# NanoShield.net
KiCad netlist of a schematic drawn in EAGLE
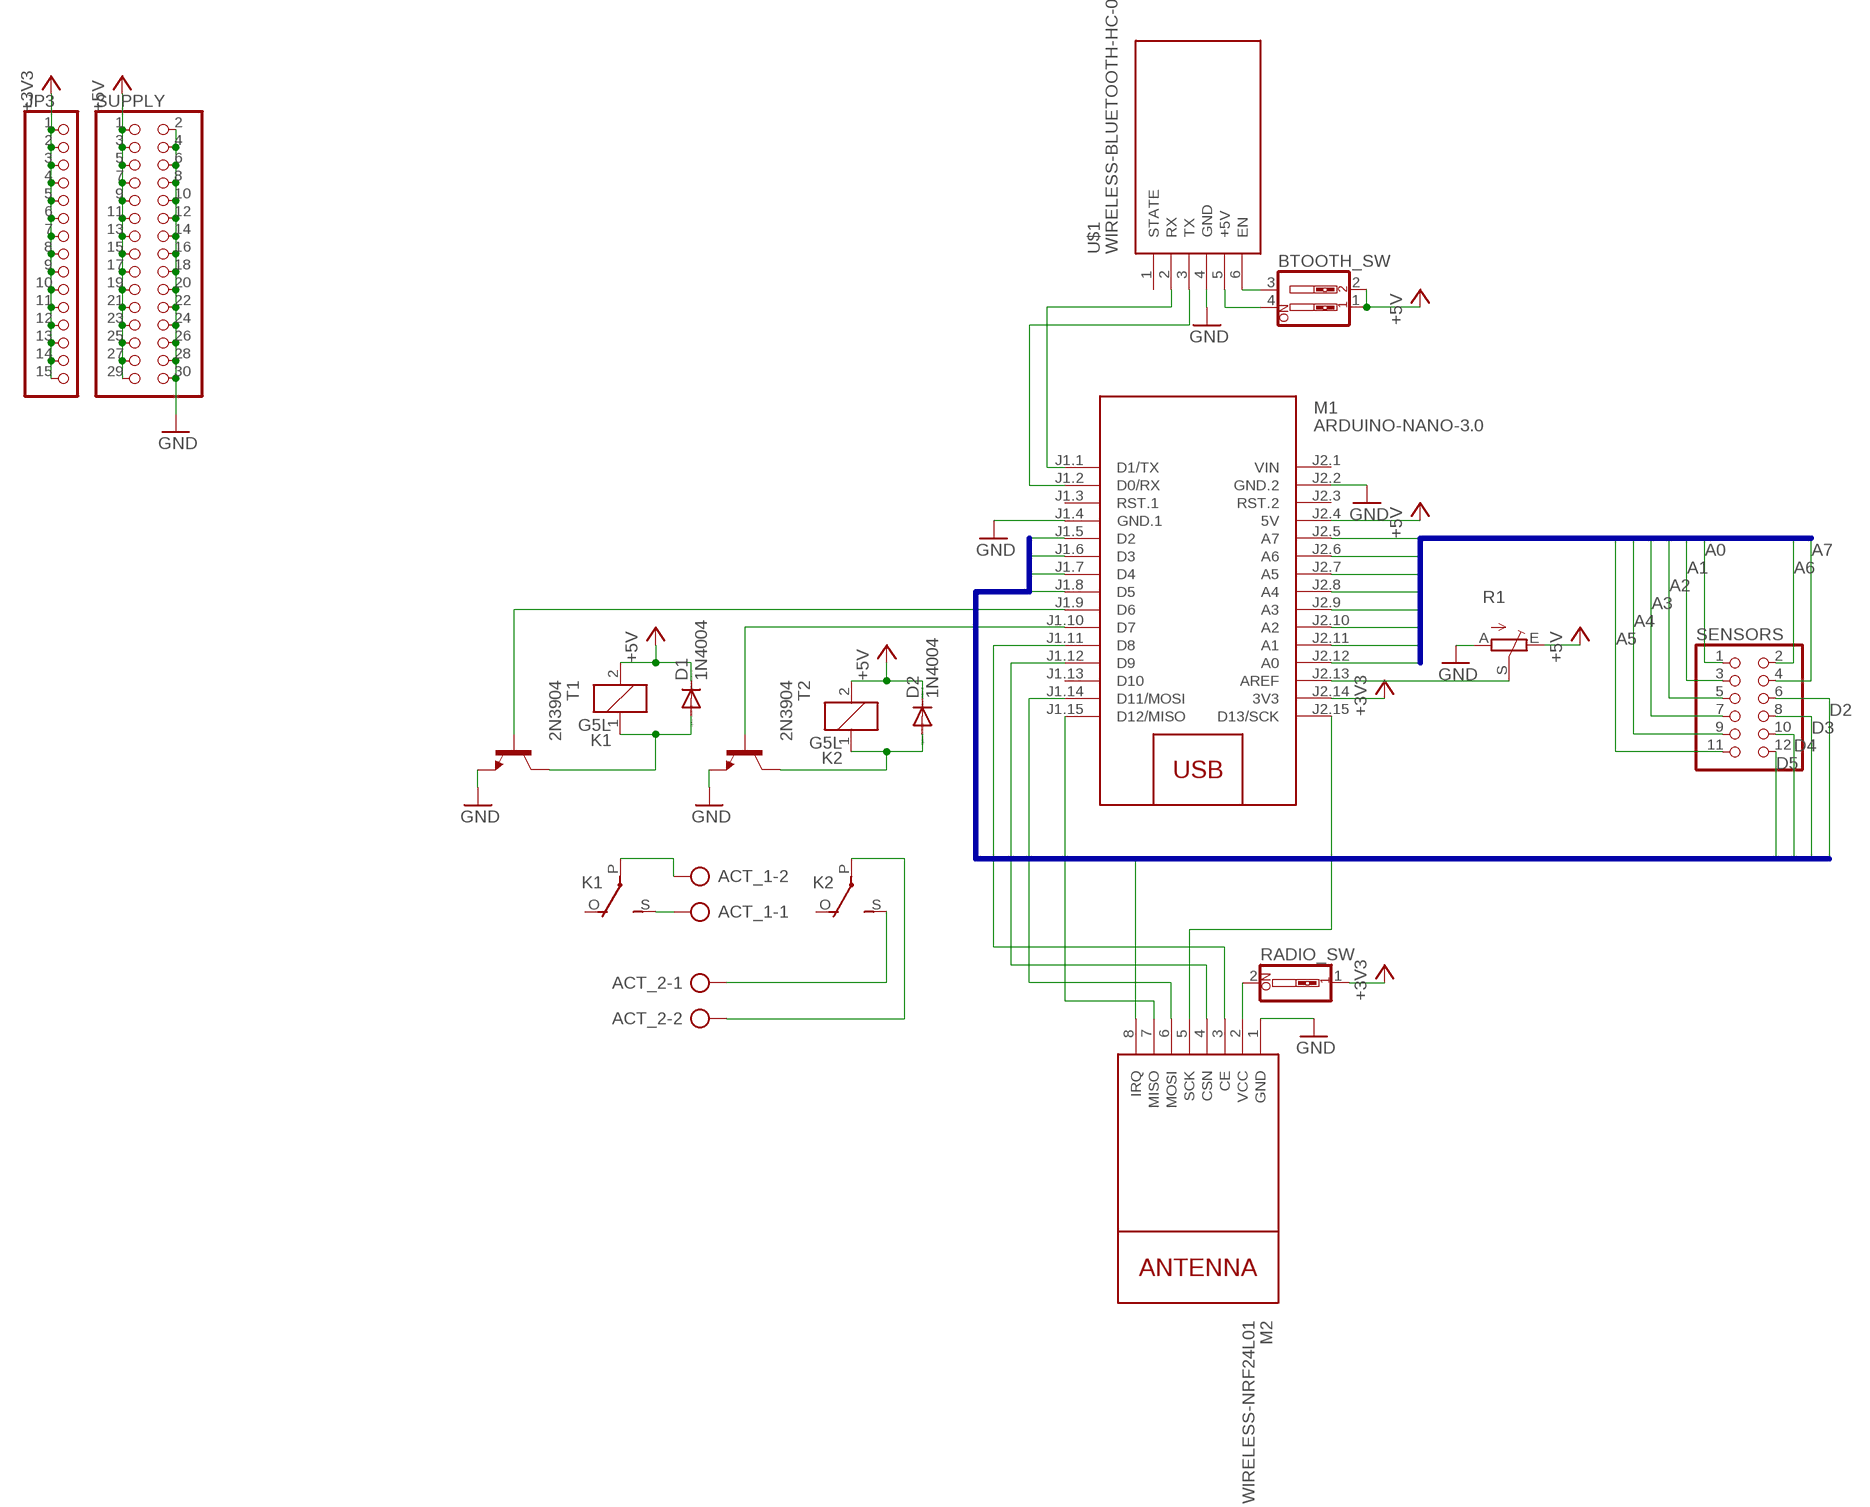
[diagram p0: schematic, sheet 1]

(export (version "E")
  (design (tool "Eeschema 10.0.6"))
  (components
    (comp (ref "ACT_1")
      (value "AK300/2")
      (footprint "eagle-import:AK300_2")
      (libsource (lib "eagle-import") (part "AK300/2"))
    )
    (comp (ref "ACT_2")
      (value "AK300/2")
      (footprint "eagle-import:AK300_2")
      (libsource (lib "eagle-import") (part "AK300/2"))
    )
    (comp (ref "BTOOTH_SW")
      (value "SW_DIP-2")
      (footprint "eagle-import:EDG-02")
      (libsource (lib "eagle-import") (part "SW_DIP-2"))
    )
    (comp (ref "D1")
      (value "1N4004")
      (footprint "eagle-import:DO41-10")
      (libsource (lib "eagle-import") (part "1N4004"))
    )
    (comp (ref "D2")
      (value "1N4004")
      (footprint "eagle-import:DO41-10")
      (libsource (lib "eagle-import") (part "1N4004"))
    )
    (comp (ref "JP3")
      (value "PINHD-1X15")
      (footprint "eagle-import:1X15")
      (libsource (lib "eagle-import") (part "PINHD-1X15"))
    )
    (comp (ref "K1")
      (value "G5L")
      (footprint "eagle-import:G5LE")
      (libsource (lib "eagle-import") (part "G5L"))
    )
    (comp (ref "K2")
      (value "G5L")
      (footprint "eagle-import:G5LE")
      (libsource (lib "eagle-import") (part "G5L"))
    )
    (comp (ref "M1")
      (value "ARDUINO-NANO-3.0")
      (footprint "eagle-import:ARDUINO-NANO-3.0")
      (libsource (lib "eagle-import") (part "ARDUINO-NANO-3.0"))
    )
    (comp (ref "M2")
      (value "WIRELESS-NRF24L01")
      (footprint "eagle-import:WIRELESS-NRF24L01")
      (libsource (lib "eagle-import") (part "WIRELESS-NRF24L01"))
    )
    (comp (ref "R1")
      (value "TRIM_EU-LI10")
      (footprint "eagle-import:LI10")
      (libsource (lib "eagle-import") (part "TRIM_EU-LI10"))
    )
    (comp (ref "RADIO_SW")
      (value "SW_DIP-1")
      (footprint "eagle-import:EDG-01")
      (libsource (lib "eagle-import") (part "SW_DIP-1"))
    )
    (comp (ref "SENSORS")
      (value "PINHD-2X6")
      (footprint "eagle-import:2X06")
      (libsource (lib "eagle-import") (part "PINHD-2X6"))
    )
    (comp (ref "SUPPLY")
      (value "PINHD-2X15")
      (footprint "eagle-import:2X15")
      (libsource (lib "eagle-import") (part "PINHD-2X15"))
    )
    (comp (ref "T1")
      (value "2N3904")
      (footprint "eagle-import:TO92")
      (libsource (lib "eagle-import") (part "2N3904"))
    )
    (comp (ref "T2")
      (value "2N3904")
      (footprint "eagle-import:TO92")
      (libsource (lib "eagle-import") (part "2N3904"))
    )
    (comp (ref "U$1")
      (value "WIRELESS-BLUETOOTH-HC-05")
      (footprint "eagle-import:WIRELESS-BLUETOOTH-HC-05")
      (libsource (lib "eagle-import") (part "WIRELESS-BLUETOOTH-HC-05"))
    )
  )
  (nets
    (net (code "1") (name "+3V3") (class "Default")
      (node (ref "JP3") (pin "1") (pinfunction "1_1") (pintype "passive"))
      (node (ref "JP3") (pin "10") (pinfunction "10_10") (pintype "passive"))
      (node (ref "JP3") (pin "11") (pinfunction "11_11") (pintype "passive"))
      (node (ref "JP3") (pin "12") (pinfunction "12_12") (pintype "passive"))
      (node (ref "JP3") (pin "13") (pinfunction "13_13") (pintype "passive"))
      (node (ref "JP3") (pin "14") (pinfunction "14_14") (pintype "passive"))
      (node (ref "JP3") (pin "15") (pinfunction "15_15") (pintype "passive"))
      (node (ref "JP3") (pin "2") (pinfunction "2_2") (pintype "passive"))
      (node (ref "JP3") (pin "3") (pinfunction "3_3") (pintype "passive"))
      (node (ref "JP3") (pin "4") (pinfunction "4_4") (pintype "passive"))
      (node (ref "JP3") (pin "5") (pinfunction "5_5") (pintype "passive"))
      (node (ref "JP3") (pin "6") (pinfunction "6_6") (pintype "passive"))
      (node (ref "JP3") (pin "7") (pinfunction "7_7") (pintype "passive"))
      (node (ref "JP3") (pin "8") (pinfunction "8_8") (pintype "passive"))
      (node (ref "JP3") (pin "9") (pinfunction "9_9") (pintype "passive"))
      (node (ref "M1") (pin "J2.14") (pinfunction "3V3_J2.14") (pintype "power_in"))
      (node (ref "RADIO_SW") (pin "1") (pinfunction "1_1") (pintype "passive"))
    )
    (net (code "2") (name "+5V") (class "Default")
      (node (ref "BTOOTH_SW") (pin "1") (pinfunction "1_1") (pintype "passive"))
      (node (ref "BTOOTH_SW") (pin "2") (pinfunction "2_2") (pintype "passive"))
      (node (ref "D1") (pin "C") (pinfunction "C_C") (pintype "passive"))
      (node (ref "D2") (pin "C") (pinfunction "C_C") (pintype "passive"))
      (node (ref "K1") (pin "2") (pinfunction "2_2") (pintype "passive"))
      (node (ref "K2") (pin "2") (pinfunction "2_2") (pintype "passive"))
      (node (ref "M1") (pin "J2.4") (pinfunction "5V_J2.4") (pintype "power_in"))
      (node (ref "R1") (pin "E") (pinfunction "E_E") (pintype "passive"))
      (node (ref "SUPPLY") (pin "1") (pinfunction "1_1") (pintype "passive"))
      (node (ref "SUPPLY") (pin "11") (pinfunction "11_11") (pintype "passive"))
      (node (ref "SUPPLY") (pin "13") (pinfunction "13_13") (pintype "passive"))
      (node (ref "SUPPLY") (pin "15") (pinfunction "15_15") (pintype "passive"))
      (node (ref "SUPPLY") (pin "17") (pinfunction "17_17") (pintype "passive"))
      (node (ref "SUPPLY") (pin "19") (pinfunction "19_19") (pintype "passive"))
      (node (ref "SUPPLY") (pin "21") (pinfunction "21_21") (pintype "passive"))
      (node (ref "SUPPLY") (pin "23") (pinfunction "23_23") (pintype "passive"))
      (node (ref "SUPPLY") (pin "25") (pinfunction "25_25") (pintype "passive"))
      (node (ref "SUPPLY") (pin "27") (pinfunction "27_27") (pintype "passive"))
      (node (ref "SUPPLY") (pin "29") (pinfunction "29_29") (pintype "passive"))
      (node (ref "SUPPLY") (pin "3") (pinfunction "3_3") (pintype "passive"))
      (node (ref "SUPPLY") (pin "5") (pinfunction "5_5") (pintype "passive"))
      (node (ref "SUPPLY") (pin "7") (pinfunction "7_7") (pintype "passive"))
      (node (ref "SUPPLY") (pin "9") (pinfunction "9_9") (pintype "passive"))
    )
    (net (code "3") (name "/A0") (class "Default")
      (node (ref "M1") (pin "J2.12") (pinfunction "A0_J2.12") (pintype "bidirectional"))
      (node (ref "SENSORS") (pin "1") (pinfunction "1_1") (pintype "passive"))
    )
    (net (code "4") (name "/A1") (class "Default")
      (node (ref "M1") (pin "J2.11") (pinfunction "A1_J2.11") (pintype "bidirectional"))
      (node (ref "SENSORS") (pin "3") (pinfunction "3_3") (pintype "passive"))
    )
    (net (code "5") (name "/A2") (class "Default")
      (node (ref "M1") (pin "J2.10") (pinfunction "A2_J2.10") (pintype "bidirectional"))
      (node (ref "SENSORS") (pin "5") (pinfunction "5_5") (pintype "passive"))
    )
    (net (code "6") (name "/A3") (class "Default")
      (node (ref "M1") (pin "J2.9") (pinfunction "A3_J2.9") (pintype "bidirectional"))
      (node (ref "SENSORS") (pin "7") (pinfunction "7_7") (pintype "passive"))
    )
    (net (code "7") (name "/A4") (class "Default")
      (node (ref "M1") (pin "J2.8") (pinfunction "A4_J2.8") (pintype "bidirectional"))
      (node (ref "SENSORS") (pin "9") (pinfunction "9_9") (pintype "passive"))
    )
    (net (code "8") (name "/A5") (class "Default")
      (node (ref "M1") (pin "J2.7") (pinfunction "A5_J2.7") (pintype "bidirectional"))
      (node (ref "SENSORS") (pin "11") (pinfunction "11_11") (pintype "passive"))
    )
    (net (code "9") (name "/A6") (class "Default")
      (node (ref "M1") (pin "J2.6") (pinfunction "A6_J2.6") (pintype "bidirectional"))
      (node (ref "SENSORS") (pin "2") (pinfunction "2_2") (pintype "passive"))
    )
    (net (code "10") (name "/A7") (class "Default")
      (node (ref "M1") (pin "J2.5") (pinfunction "A7_J2.5") (pintype "bidirectional"))
      (node (ref "SENSORS") (pin "4") (pinfunction "4_4") (pintype "passive"))
    )
    (net (code "11") (name "/D2") (class "Default")
      (node (ref "M1") (pin "J1.5") (pinfunction "D2_J1.5") (pintype "bidirectional"))
      (node (ref "M2") (pin "8") (pinfunction "IRQ_8") (pintype "bidirectional"))
      (node (ref "SENSORS") (pin "6") (pinfunction "6_6") (pintype "passive"))
    )
    (net (code "12") (name "/D3") (class "Default")
      (node (ref "M1") (pin "J1.6") (pinfunction "D3_J1.6") (pintype "bidirectional"))
      (node (ref "SENSORS") (pin "8") (pinfunction "8_8") (pintype "passive"))
    )
    (net (code "13") (name "/D4") (class "Default")
      (node (ref "M1") (pin "J1.7") (pinfunction "D4_J1.7") (pintype "bidirectional"))
      (node (ref "SENSORS") (pin "10") (pinfunction "10_10") (pintype "passive"))
    )
    (net (code "14") (name "/D5") (class "Default")
      (node (ref "M1") (pin "J1.8") (pinfunction "D5_J1.8") (pintype "bidirectional"))
      (node (ref "SENSORS") (pin "12") (pinfunction "12_12") (pintype "passive"))
    )
    (net (code "15") (name "/VIN") (class "Default")
      (node (ref "M1") (pin "J2.1") (pinfunction "VIN_J2.1") (pintype "power_in"))
    )
    (net (code "16") (name "GND") (class "Default")
      (node (ref "M1") (pin "J1.4") (pinfunction "GND.1_J1.4") (pintype "power_in"))
      (node (ref "M1") (pin "J2.2") (pinfunction "GND.2_J2.2") (pintype "power_in"))
      (node (ref "M2") (pin "1") (pinfunction "GND_1") (pintype "power_in"))
      (node (ref "R1") (pin "A") (pinfunction "A_A") (pintype "passive"))
      (node (ref "SUPPLY") (pin "10") (pinfunction "10_10") (pintype "passive"))
      (node (ref "SUPPLY") (pin "12") (pinfunction "12_12") (pintype "passive"))
      (node (ref "SUPPLY") (pin "14") (pinfunction "14_14") (pintype "passive"))
      (node (ref "SUPPLY") (pin "16") (pinfunction "16_16") (pintype "passive"))
      (node (ref "SUPPLY") (pin "18") (pinfunction "18_18") (pintype "passive"))
      (node (ref "SUPPLY") (pin "2") (pinfunction "2_2") (pintype "passive"))
      (node (ref "SUPPLY") (pin "20") (pinfunction "20_20") (pintype "passive"))
      (node (ref "SUPPLY") (pin "22") (pinfunction "22_22") (pintype "passive"))
      (node (ref "SUPPLY") (pin "24") (pinfunction "24_24") (pintype "passive"))
      (node (ref "SUPPLY") (pin "26") (pinfunction "26_26") (pintype "passive"))
      (node (ref "SUPPLY") (pin "28") (pinfunction "28_28") (pintype "passive"))
      (node (ref "SUPPLY") (pin "30") (pinfunction "30_30") (pintype "passive"))
      (node (ref "SUPPLY") (pin "4") (pinfunction "4_4") (pintype "passive"))
      (node (ref "SUPPLY") (pin "6") (pinfunction "6_6") (pintype "passive"))
      (node (ref "SUPPLY") (pin "8") (pinfunction "8_8") (pintype "passive"))
      (node (ref "T1") (pin "3") (pinfunction "E_3") (pintype "passive"))
      (node (ref "T2") (pin "3") (pinfunction "E_3") (pintype "passive"))
      (node (ref "U$1") (pin "4") (pinfunction "GND_4") (pintype "power_in"))
    )
    (net (code "17") (name "Net-(ACT_1A-KL)") (class "Default")
      (node (ref "ACT_1") (pin "1") (pinfunction "KL_1") (pintype "passive"))
      (node (ref "K1") (pin "S") (pinfunction "S_S") (pintype "passive"))
    )
    (net (code "18") (name "Net-(ACT_1B-KL)") (class "Default")
      (node (ref "ACT_1") (pin "2") (pinfunction "KL_2") (pintype "passive"))
      (node (ref "K1") (pin "P") (pinfunction "P_P") (pintype "passive"))
    )
    (net (code "19") (name "Net-(ACT_2A-KL)") (class "Default")
      (node (ref "ACT_2") (pin "1") (pinfunction "KL_1") (pintype "passive"))
      (node (ref "K2") (pin "S") (pinfunction "S_S") (pintype "passive"))
    )
    (net (code "20") (name "Net-(ACT_2B-KL)") (class "Default")
      (node (ref "ACT_2") (pin "2") (pinfunction "KL_2") (pintype "passive"))
      (node (ref "K2") (pin "P") (pinfunction "P_P") (pintype "passive"))
    )
    (net (code "21") (name "Net-(M1-AREF)") (class "Default")
      (node (ref "M1") (pin "J2.13") (pinfunction "AREF_J2.13") (pintype "bidirectional"))
      (node (ref "R1") (pin "S") (pinfunction "S_S") (pintype "passive"))
    )
    (net (code "22") (name "Net-(M1-D0{slash}RX)") (class "Default")
      (node (ref "M1") (pin "J1.2") (pinfunction "D0/RX_J1.2") (pintype "bidirectional"))
      (node (ref "U$1") (pin "3") (pinfunction "TX_3") (pintype "bidirectional"))
    )
    (net (code "23") (name "Net-(M1-D1{slash}TX)") (class "Default")
      (node (ref "M1") (pin "J1.1") (pinfunction "D1/TX_J1.1") (pintype "bidirectional"))
      (node (ref "U$1") (pin "2") (pinfunction "RX_2") (pintype "bidirectional"))
    )
    (net (code "24") (name "Net-(M1-D6)") (class "Default")
      (node (ref "M1") (pin "J1.9") (pinfunction "D6_J1.9") (pintype "bidirectional"))
      (node (ref "T1") (pin "2") (pinfunction "B_2") (pintype "passive"))
    )
    (net (code "25") (name "Net-(M1-D7)") (class "Default")
      (node (ref "M1") (pin "J1.10") (pinfunction "D7_J1.10") (pintype "bidirectional"))
      (node (ref "T2") (pin "2") (pinfunction "B_2") (pintype "passive"))
    )
    (net (code "26") (name "Net-(M1-D8)") (class "Default")
      (node (ref "M1") (pin "J1.11") (pinfunction "D8_J1.11") (pintype "bidirectional"))
      (node (ref "M2") (pin "3") (pinfunction "CE_3") (pintype "bidirectional"))
    )
    (net (code "27") (name "Net-(M1-D9)") (class "Default")
      (node (ref "M1") (pin "J1.12") (pinfunction "D9_J1.12") (pintype "bidirectional"))
      (node (ref "M2") (pin "4") (pinfunction "CSN_4") (pintype "bidirectional"))
    )
    (net (code "28") (name "Net-(M1-D11{slash}MOSI)") (class "Default")
      (node (ref "M1") (pin "J1.14") (pinfunction "D11/MOSI_J1.14") (pintype "bidirectional"))
      (node (ref "M2") (pin "6") (pinfunction "MOSI_6") (pintype "bidirectional"))
    )
    (net (code "29") (name "Net-(M1-D12{slash}MISO)") (class "Default")
      (node (ref "M1") (pin "J1.15") (pinfunction "D12/MISO_J1.15") (pintype "bidirectional"))
      (node (ref "M2") (pin "7") (pinfunction "MISO_7") (pintype "bidirectional"))
    )
    (net (code "30") (name "Net-(M1-D13{slash}SCK)") (class "Default")
      (node (ref "M1") (pin "J2.15") (pinfunction "D13/SCK_J2.15") (pintype "bidirectional"))
      (node (ref "M2") (pin "5") (pinfunction "SCK_5") (pintype "bidirectional"))
    )
    (net (code "31") (name "Net-(M2-VCC)") (class "Default")
      (node (ref "M2") (pin "2") (pinfunction "VCC_2") (pintype "power_in"))
      (node (ref "RADIO_SW") (pin "2") (pinfunction "2_2") (pintype "passive"))
    )
    (net (code "32") (name "Net-(T1-C)") (class "Default")
      (node (ref "D1") (pin "A") (pinfunction "A_A") (pintype "passive"))
      (node (ref "K1") (pin "1") (pinfunction "1_1") (pintype "passive"))
      (node (ref "T1") (pin "1") (pinfunction "C_1") (pintype "passive"))
    )
    (net (code "33") (name "Net-(T2-C)") (class "Default")
      (node (ref "D2") (pin "A") (pinfunction "A_A") (pintype "passive"))
      (node (ref "K2") (pin "1") (pinfunction "1_1") (pintype "passive"))
      (node (ref "T2") (pin "1") (pinfunction "C_1") (pintype "passive"))
    )
    (net (code "34") (name "Net-(U$1-+5V)") (class "Default")
      (node (ref "BTOOTH_SW") (pin "4") (pinfunction "4_4") (pintype "passive"))
      (node (ref "U$1") (pin "5") (pinfunction "+5V_5") (pintype "power_in"))
    )
    (net (code "35") (name "Net-(U$1-EN)") (class "Default")
      (node (ref "BTOOTH_SW") (pin "3") (pinfunction "3_3") (pintype "passive"))
      (node (ref "U$1") (pin "6") (pinfunction "EN_6") (pintype "bidirectional"))
    )
    (net (code "36") (name "unconnected-(K1-PadO)") (class "Default")
      (node (ref "K1") (pin "O") (pinfunction "O_O") (pintype "passive"))
    )
    (net (code "37") (name "unconnected-(K2-PadO)") (class "Default")
      (node (ref "K2") (pin "O") (pinfunction "O_O") (pintype "passive"))
    )
    (net (code "38") (name "unconnected-(M1-D10-PadJ1.13)") (class "Default")
      (node (ref "M1") (pin "J1.13") (pinfunction "D10_J1.13") (pintype "bidirectional"))
    )
    (net (code "39") (name "unconnected-(M1-RST.1-PadJ1.3)") (class "Default")
      (node (ref "M1") (pin "J1.3") (pinfunction "RST.1_J1.3") (pintype "bidirectional"))
    )
    (net (code "40") (name "unconnected-(M1-RST.2-PadJ2.3)") (class "Default")
      (node (ref "M1") (pin "J2.3") (pinfunction "RST.2_J2.3") (pintype "bidirectional"))
    )
    (net (code "41") (name "unconnected-(U$1-STATE-Pad1)") (class "Default")
      (node (ref "U$1") (pin "1") (pinfunction "STATE_1") (pintype "bidirectional"))
    )
  )
)
